# baseSchematicv2sch.net
KiCad netlist of a schematic drawn in EAGLE
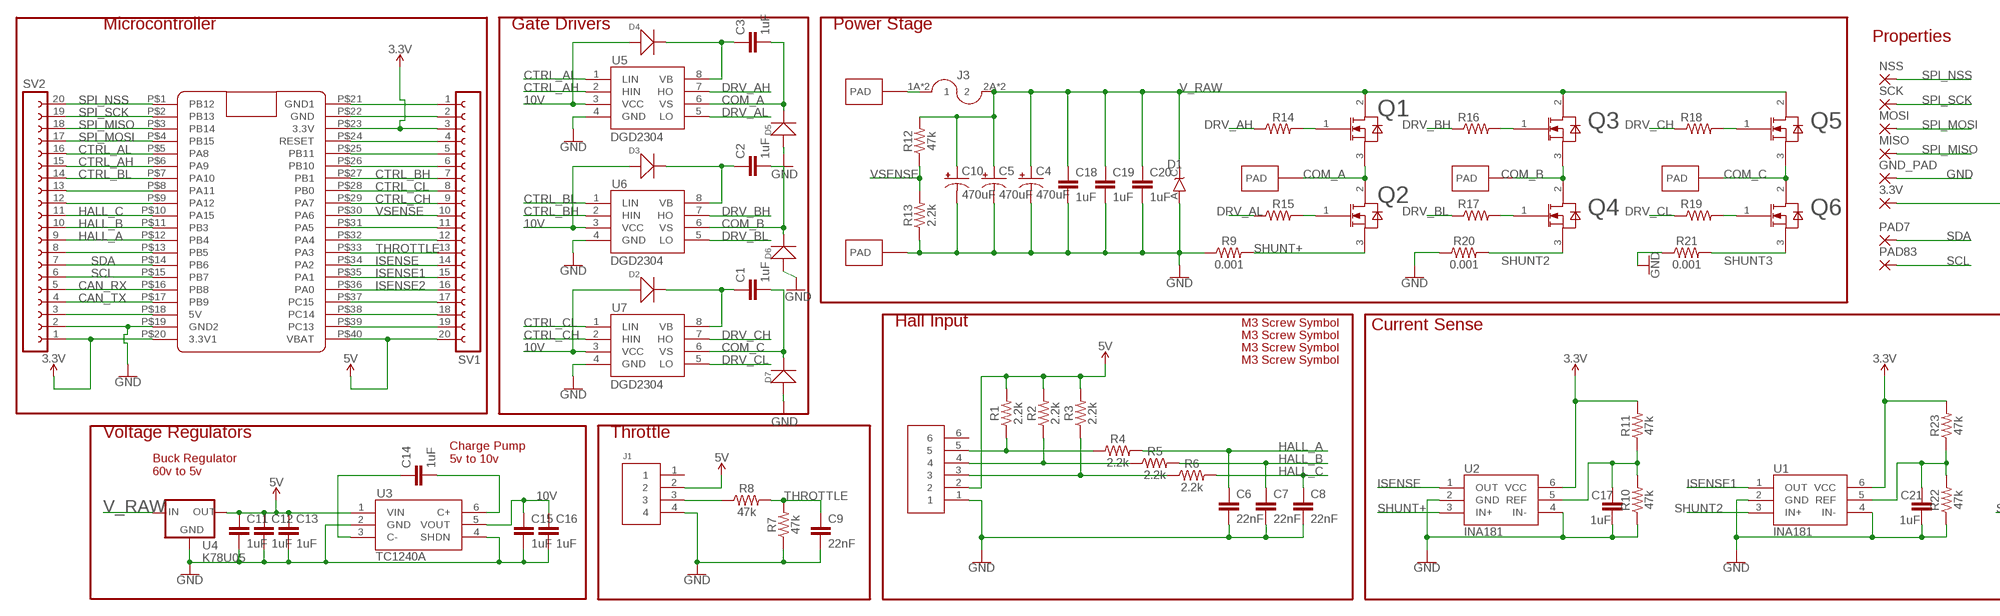
[diagram p0: schematic, sheet 1, part 1 of 2]
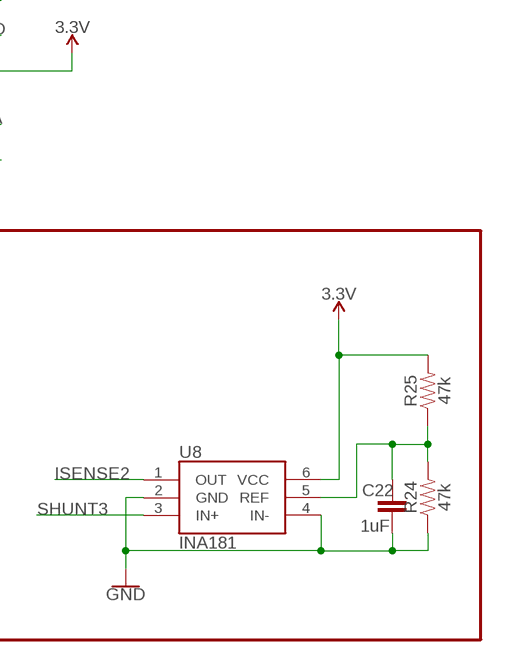
[diagram p1: schematic, sheet 1, part 2 of 2]

(export (version "E")
  (design (tool "Eeschema 10.0.6"))
  (components
    (comp (ref "3.3V")
      (value "2,15/1,0")
      (footprint "eagle-import:2,15_1,0")
      (libsource (lib "eagle-import") (part "2,15/1,0"))
    )
    (comp (ref "C1")
      (value "1uF")
      (footprint "eagle-import:1206")
      (libsource (lib "eagle-import") (part "1.0UF-1206-50V-10%"))
    )
    (comp (ref "C2")
      (value "1uF")
      (footprint "eagle-import:1206")
      (libsource (lib "eagle-import") (part "1.0UF-1206-50V-10%"))
    )
    (comp (ref "C3")
      (value "1uF")
      (footprint "eagle-import:1206")
      (libsource (lib "eagle-import") (part "1.0UF-1206-50V-10%"))
    )
    (comp (ref "C4")
      (value "470uF")
      (footprint "eagle-import:CPOL-RADIAL-5MM-10MM")
      (libsource (lib "eagle-import") (part "1000UF-RADIAL-5MM-25V-20%"))
    )
    (comp (ref "C5")
      (value "470uF")
      (footprint "eagle-import:CPOL-RADIAL-5MM-10MM")
      (libsource (lib "eagle-import") (part "1000UF-RADIAL-5MM-25V-20%"))
    )
    (comp (ref "C6")
      (value "22nF")
      (footprint "eagle-import:1206")
      (libsource (lib "eagle-import") (part "1.0UF-1206-50V-10%"))
    )
    (comp (ref "C7")
      (value "22nF")
      (footprint "eagle-import:1206")
      (libsource (lib "eagle-import") (part "1.0UF-1206-50V-10%"))
    )
    (comp (ref "C8")
      (value "22nF")
      (footprint "eagle-import:1206")
      (libsource (lib "eagle-import") (part "1.0UF-1206-50V-10%"))
    )
    (comp (ref "C9")
      (value "22nF")
      (footprint "eagle-import:1206")
      (libsource (lib "eagle-import") (part "1.0UF-1206-50V-10%"))
    )
    (comp (ref "C10")
      (value "470uF")
      (footprint "eagle-import:CPOL-RADIAL-5MM-10MM")
      (libsource (lib "eagle-import") (part "1000UF-RADIAL-5MM-25V-20%"))
    )
    (comp (ref "C11")
      (value "1uF")
      (footprint "eagle-import:1206")
      (libsource (lib "eagle-import") (part "1.0UF-1206-50V-10%"))
    )
    (comp (ref "C12")
      (value "1uF")
      (footprint "eagle-import:1206")
      (libsource (lib "eagle-import") (part "1.0UF-1206-50V-10%"))
    )
    (comp (ref "C13")
      (value "1uF")
      (footprint "eagle-import:1206")
      (libsource (lib "eagle-import") (part "1.0UF-1206-50V-10%"))
    )
    (comp (ref "C14")
      (value "1uF")
      (footprint "eagle-import:1206")
      (libsource (lib "eagle-import") (part "1.0UF-1206-50V-10%"))
    )
    (comp (ref "C15")
      (value "1uF")
      (footprint "eagle-import:1206")
      (libsource (lib "eagle-import") (part "1.0UF-1206-50V-10%"))
    )
    (comp (ref "C16")
      (value "1uF")
      (footprint "eagle-import:1206")
      (libsource (lib "eagle-import") (part "1.0UF-1206-50V-10%"))
    )
    (comp (ref "C17")
      (value "1uF")
      (footprint "eagle-import:1206")
      (libsource (lib "eagle-import") (part "1.0UF-1206-50V-10%"))
    )
    (comp (ref "C18")
      (value "1uF")
      (footprint "eagle-import:1206")
      (libsource (lib "eagle-import") (part "1.0UF-1206-50V-10%"))
    )
    (comp (ref "C19")
      (value "1uF")
      (footprint "eagle-import:1206")
      (libsource (lib "eagle-import") (part "1.0UF-1206-50V-10%"))
    )
    (comp (ref "C20")
      (value "1uF")
      (footprint "eagle-import:1206")
      (libsource (lib "eagle-import") (part "1.0UF-1206-50V-10%"))
    )
    (comp (ref "C21")
      (value "1uF")
      (footprint "eagle-import:1206")
      (libsource (lib "eagle-import") (part "1.0UF-1206-50V-10%"))
    )
    (comp (ref "C22")
      (value "1uF")
      (footprint "eagle-import:1206")
      (libsource (lib "eagle-import") (part "1.0UF-1206-50V-10%"))
    )
    (comp (ref "D1")
      (value "TVS")
      (footprint "eagle-import:DO-214AC")
      (libsource (lib "eagle-import") (part "TVS_UNIDO-214AC"))
    )
    (comp (ref "D2")
      (value "SMD-DIODE-100V-200MA(SOD-123)")
      (footprint "eagle-import:SOD-123")
      (fields (field (name "MPN") "MMSD4148"))
      (libsource (lib "eagle-import") (part "SMD-DIODE-100V-200MA(SOD-123)"))
    )
    (comp (ref "D3")
      (value "SMD-DIODE-100V-200MA(SOD-123)")
      (footprint "eagle-import:SOD-123")
      (fields (field (name "MPN") "MMSD4148"))
      (libsource (lib "eagle-import") (part "SMD-DIODE-100V-200MA(SOD-123)"))
    )
    (comp (ref "D4")
      (value "SMD-DIODE-100V-200MA(SOD-123)")
      (footprint "eagle-import:SOD-123")
      (fields (field (name "MPN") "MMSD4148"))
      (libsource (lib "eagle-import") (part "SMD-DIODE-100V-200MA(SOD-123)"))
    )
    (comp (ref "D5")
      (value "SMD-DIODE-100V-200MA(SOD-123)")
      (footprint "eagle-import:SOD-123")
      (fields (field (name "MPN") "MMSD4148"))
      (libsource (lib "eagle-import") (part "SMD-DIODE-100V-200MA(SOD-123)"))
    )
    (comp (ref "D6")
      (value "SMD-DIODE-100V-200MA(SOD-123)")
      (footprint "eagle-import:SOD-123")
      (fields (field (name "MPN") "MMSD4148"))
      (libsource (lib "eagle-import") (part "SMD-DIODE-100V-200MA(SOD-123)"))
    )
    (comp (ref "D7")
      (value "SMD-DIODE-100V-200MA(SOD-123)")
      (footprint "eagle-import:SOD-123")
      (fields (field (name "MPN") "MMSD4148"))
      (libsource (lib "eagle-import") (part "SMD-DIODE-100V-200MA(SOD-123)"))
    )
    (comp (ref "GND_PAD")
      (value "2,15/1,0")
      (footprint "eagle-import:2,15_1,0")
      (libsource (lib "eagle-import") (part "2,15/1,0"))
    )
    (comp (ref "J1")
      (value "HEADER4VALULOK")
      (footprint "eagle-import:4PINVALULOK")
      (libsource (lib "eagle-import") (part "HEADER4VALULOK"))
    )
    (comp (ref "J2")
      (value "HEADER6")
      (footprint "eagle-import:6PINVALULOK")
      (libsource (lib "eagle-import") (part "HEADER6"))
    )
    (comp (ref "J3")
      (value "FUSE")
      (footprint "eagle-import:AUTO_FUSE")
      (libsource (lib "eagle-import") (part "FUSE"))
    )
    (comp (ref "MISO")
      (value "2,15/1,0")
      (footprint "eagle-import:2,15_1,0")
      (libsource (lib "eagle-import") (part "2,15/1,0"))
    )
    (comp (ref "MOSI")
      (value "2,15/1,0")
      (footprint "eagle-import:2,15_1,0")
      (libsource (lib "eagle-import") (part "2,15/1,0"))
    )
    (comp (ref "NSS")
      (value "2,15/1,0")
      (footprint "eagle-import:2,15_1,0")
      (libsource (lib "eagle-import") (part "2,15/1,0"))
    )
    (comp (ref "PAD7")
      (value "2,15/1,0")
      (footprint "eagle-import:2,15_1,0")
      (libsource (lib "eagle-import") (part "2,15/1,0"))
    )
    (comp (ref "PAD83")
      (value "2,15/1,0")
      (footprint "eagle-import:2,15_1,0")
      (libsource (lib "eagle-import") (part "2,15/1,0"))
    )
    (comp (ref "Q1")
      (value "IRF135S203")
      (footprint "eagle-import:TO254P1524X508-4_3N")
      (libsource (lib "eagle-import") (part "IRF135S203"))
    )
    (comp (ref "Q2")
      (value "IRF135S203")
      (footprint "eagle-import:TO254P1524X508-4_3N")
      (libsource (lib "eagle-import") (part "IRF135S203"))
    )
    (comp (ref "Q3")
      (value "IRF135S203")
      (footprint "eagle-import:TO254P1524X508-4_3N")
      (libsource (lib "eagle-import") (part "IRF135S203"))
    )
    (comp (ref "Q4")
      (value "IRF135S203")
      (footprint "eagle-import:TO254P1524X508-4_3N")
      (libsource (lib "eagle-import") (part "IRF135S203"))
    )
    (comp (ref "Q5")
      (value "IRF135S203")
      (footprint "eagle-import:TO254P1524X508-4_3N")
      (libsource (lib "eagle-import") (part "IRF135S203"))
    )
    (comp (ref "Q6")
      (value "IRF135S203")
      (footprint "eagle-import:TO254P1524X508-4_3N")
      (libsource (lib "eagle-import") (part "IRF135S203"))
    )
    (comp (ref "R1")
      (value "2.2k")
      (footprint "eagle-import:1206")
      (libsource (lib "eagle-import") (part "RESISTOR1206"))
    )
    (comp (ref "R2")
      (value "2.2k")
      (footprint "eagle-import:1206")
      (libsource (lib "eagle-import") (part "RESISTOR1206"))
    )
    (comp (ref "R3")
      (value "2.2k")
      (footprint "eagle-import:1206")
      (libsource (lib "eagle-import") (part "RESISTOR1206"))
    )
    (comp (ref "R4")
      (value "2.2k")
      (footprint "eagle-import:1206")
      (libsource (lib "eagle-import") (part "RESISTOR1206"))
    )
    (comp (ref "R5")
      (value "2.2k")
      (footprint "eagle-import:1206")
      (libsource (lib "eagle-import") (part "RESISTOR1206"))
    )
    (comp (ref "R6")
      (value "2.2k")
      (footprint "eagle-import:1206")
      (libsource (lib "eagle-import") (part "RESISTOR1206"))
    )
    (comp (ref "R7")
      (value "47k")
      (footprint "eagle-import:1206")
      (libsource (lib "eagle-import") (part "RESISTOR1206"))
    )
    (comp (ref "R8")
      (value "47k")
      (footprint "eagle-import:1206")
      (libsource (lib "eagle-import") (part "RESISTOR1206"))
    )
    (comp (ref "R9")
      (value "0.001")
      (footprint "eagle-import:R2512")
      (libsource (lib "eagle-import") (part "RESISTOR"))
    )
    (comp (ref "R10")
      (value "47k")
      (footprint "eagle-import:1206")
      (libsource (lib "eagle-import") (part "RESISTOR1206"))
    )
    (comp (ref "R11")
      (value "47k")
      (footprint "eagle-import:1206")
      (libsource (lib "eagle-import") (part "RESISTOR1206"))
    )
    (comp (ref "R12")
      (value "47k")
      (footprint "eagle-import:1206")
      (libsource (lib "eagle-import") (part "RESISTOR1206"))
    )
    (comp (ref "R13")
      (value "2.2k")
      (footprint "eagle-import:1206")
      (libsource (lib "eagle-import") (part "RESISTOR1206"))
    )
    (comp (ref "R14")
      (value "R-US_R1206")
      (footprint "eagle-import:R1206")
      (libsource (lib "eagle-import") (part "R-US_R1206"))
    )
    (comp (ref "R15")
      (value "R-US_R1206")
      (footprint "eagle-import:R1206")
      (libsource (lib "eagle-import") (part "R-US_R1206"))
    )
    (comp (ref "R16")
      (value "R-US_R1206")
      (footprint "eagle-import:R1206")
      (libsource (lib "eagle-import") (part "R-US_R1206"))
    )
    (comp (ref "R17")
      (value "R-US_R1206")
      (footprint "eagle-import:R1206")
      (libsource (lib "eagle-import") (part "R-US_R1206"))
    )
    (comp (ref "R18")
      (value "R-US_R1206")
      (footprint "eagle-import:R1206")
      (libsource (lib "eagle-import") (part "R-US_R1206"))
    )
    (comp (ref "R19")
      (value "R-US_R1206")
      (footprint "eagle-import:R1206")
      (libsource (lib "eagle-import") (part "R-US_R1206"))
    )
    (comp (ref "R20")
      (value "0.001")
      (footprint "eagle-import:R2512")
      (libsource (lib "eagle-import") (part "RESISTOR"))
    )
    (comp (ref "R21")
      (value "0.001")
      (footprint "eagle-import:R2512")
      (libsource (lib "eagle-import") (part "RESISTOR"))
    )
    (comp (ref "R22")
      (value "47k")
      (footprint "eagle-import:1206")
      (libsource (lib "eagle-import") (part "RESISTOR1206"))
    )
    (comp (ref "R23")
      (value "47k")
      (footprint "eagle-import:1206")
      (libsource (lib "eagle-import") (part "RESISTOR1206"))
    )
    (comp (ref "R24")
      (value "47k")
      (footprint "eagle-import:1206")
      (libsource (lib "eagle-import") (part "RESISTOR1206"))
    )
    (comp (ref "R25")
      (value "47k")
      (footprint "eagle-import:1206")
      (libsource (lib "eagle-import") (part "RESISTOR1206"))
    )
    (comp (ref "SCK")
      (value "2,15/1,0")
      (footprint "eagle-import:2,15_1,0")
      (libsource (lib "eagle-import") (part "2,15/1,0"))
    )
    (comp (ref "SV1")
      (value "FE20-1")
      (footprint "eagle-import:FE20")
      (libsource (lib "eagle-import") (part "FE20-1"))
    )
    (comp (ref "SV2")
      (value "FE20-1")
      (footprint "eagle-import:FE20")
      (libsource (lib "eagle-import") (part "FE20-1"))
    )
    (comp (ref "U$1")
      (value "BLUE_PILL")
      (footprint "eagle-import:BLUE_PILL")
      (libsource (lib "eagle-import") (part "BLUE_PILL"))
    )
    (comp (ref "U$4")
      (value "PAD")
      (footprint "eagle-import:PAD")
      (libsource (lib "eagle-import") (part "PAD"))
    )
    (comp (ref "U$5")
      (value "PAD")
      (footprint "eagle-import:PAD")
      (libsource (lib "eagle-import") (part "PAD"))
    )
    (comp (ref "U$6")
      (value "PAD")
      (footprint "eagle-import:PAD")
      (libsource (lib "eagle-import") (part "PAD"))
    )
    (comp (ref "U$7")
      (value "PAD")
      (footprint "eagle-import:PAD")
      (libsource (lib "eagle-import") (part "PAD"))
    )
    (comp (ref "U$8")
      (value "PAD")
      (footprint "eagle-import:PAD")
      (libsource (lib "eagle-import") (part "PAD"))
    )
    (comp (ref "U$10")
      (value "SCREW")
      (footprint "eagle-import:M3HOLE")
      (libsource (lib "eagle-import") (part "SCREW"))
    )
    (comp (ref "U$11")
      (value "SCREW")
      (footprint "eagle-import:M3HOLE")
      (libsource (lib "eagle-import") (part "SCREW"))
    )
    (comp (ref "U$12")
      (value "SCREW")
      (footprint "eagle-import:M3HOLE")
      (libsource (lib "eagle-import") (part "SCREW"))
    )
    (comp (ref "U$13")
      (value "SCREW")
      (footprint "eagle-import:M3HOLE")
      (libsource (lib "eagle-import") (part "SCREW"))
    )
    (comp (ref "U1")
      (value "INA181")
      (footprint "eagle-import:SOT23-6")
      (libsource (lib "eagle-import") (part "INA181"))
    )
    (comp (ref "U2")
      (value "INA181")
      (footprint "eagle-import:SOT23-6")
      (libsource (lib "eagle-import") (part "INA181"))
    )
    (comp (ref "U3")
      (value "TC1240A")
      (footprint "eagle-import:SOT23-6")
      (libsource (lib "eagle-import") (part "TC1240A"))
    )
    (comp (ref "U4")
      (value "K78U05")
      (footprint "eagle-import:V78W_BACKWARDS")
      (libsource (lib "eagle-import") (part "V_REG_78XX"))
    )
    (comp (ref "U5")
      (value "DGD2304")
      (footprint "eagle-import:SOIC8")
      (libsource (lib "eagle-import") (part "DGD2304"))
    )
    (comp (ref "U6")
      (value "DGD2304")
      (footprint "eagle-import:SOIC8")
      (libsource (lib "eagle-import") (part "DGD2304"))
    )
    (comp (ref "U7")
      (value "DGD2304")
      (footprint "eagle-import:SOIC8")
      (libsource (lib "eagle-import") (part "DGD2304"))
    )
    (comp (ref "U8")
      (value "INA181")
      (footprint "eagle-import:SOT23-6")
      (libsource (lib "eagle-import") (part "INA181"))
    )
  )
  (nets
    (net (code "1") (name "/10V") (class "Default")
      (node (ref "C15") (pin "1") (pinfunction "1_1") (pintype "passive"))
      (node (ref "C16") (pin "1") (pinfunction "1_1") (pintype "passive"))
      (node (ref "D2") (pin "+") (pinfunction "+_+") (pintype "passive"))
      (node (ref "D3") (pin "+") (pinfunction "+_+") (pintype "passive"))
      (node (ref "D4") (pin "+") (pinfunction "+_+") (pintype "passive"))
      (node (ref "U3") (pin "5") (pinfunction "VOUT_5") (pintype "bidirectional"))
      (node (ref "U5") (pin "3") (pinfunction "VCC_3") (pintype "bidirectional"))
      (node (ref "U6") (pin "3") (pinfunction "VCC_3") (pintype "bidirectional"))
      (node (ref "U7") (pin "3") (pinfunction "VCC_3") (pintype "bidirectional"))
    )
    (net (code "2") (name "/CAN_RX") (class "Default")
      (node (ref "SV2") (pin "5") (pinfunction "5_5") (pintype "passive"))
      (node (ref "U$1") (pin "P$16") (pinfunction "PB8_P$16") (pintype "bidirectional"))
    )
    (net (code "3") (name "/CAN_TX") (class "Default")
      (node (ref "SV2") (pin "4") (pinfunction "4_4") (pintype "passive"))
      (node (ref "U$1") (pin "P$17") (pinfunction "PB9_P$17") (pintype "bidirectional"))
    )
    (net (code "4") (name "/COM_A") (class "Default")
      (node (ref "C3") (pin "2") (pinfunction "2_2") (pintype "passive"))
      (node (ref "D5") (pin "-") (pinfunction "-_-") (pintype "passive"))
      (node (ref "Q1") (pin "3") (pinfunction "SOURCE_3") (pintype "passive"))
      (node (ref "Q2") (pin "2") (pinfunction "DRAIN_2") (pintype "passive"))
      (node (ref "U$6") (pin "PAD") (pinfunction "PAD_PAD") (pintype "bidirectional"))
      (node (ref "U5") (pin "6") (pinfunction "VS_6") (pintype "bidirectional"))
    )
    (net (code "5") (name "/COM_B") (class "Default")
      (node (ref "C2") (pin "2") (pinfunction "2_2") (pintype "passive"))
      (node (ref "D6") (pin "-") (pinfunction "-_-") (pintype "passive"))
      (node (ref "Q3") (pin "3") (pinfunction "SOURCE_3") (pintype "passive"))
      (node (ref "Q4") (pin "2") (pinfunction "DRAIN_2") (pintype "passive"))
      (node (ref "U$7") (pin "PAD") (pinfunction "PAD_PAD") (pintype "bidirectional"))
      (node (ref "U6") (pin "6") (pinfunction "VS_6") (pintype "bidirectional"))
    )
    (net (code "6") (name "/COM_C") (class "Default")
      (node (ref "C1") (pin "2") (pinfunction "2_2") (pintype "passive"))
      (node (ref "D7") (pin "-") (pinfunction "-_-") (pintype "passive"))
      (node (ref "Q5") (pin "3") (pinfunction "SOURCE_3") (pintype "passive"))
      (node (ref "Q6") (pin "2") (pinfunction "DRAIN_2") (pintype "passive"))
      (node (ref "U$8") (pin "PAD") (pinfunction "PAD_PAD") (pintype "bidirectional"))
      (node (ref "U7") (pin "6") (pinfunction "VS_6") (pintype "bidirectional"))
    )
    (net (code "7") (name "/CTRL_AH") (class "Default")
      (node (ref "SV2") (pin "15") (pinfunction "15_15") (pintype "passive"))
      (node (ref "U$1") (pin "P$6") (pinfunction "PA9_P$6") (pintype "bidirectional"))
      (node (ref "U5") (pin "2") (pinfunction "HIN_2") (pintype "bidirectional"))
    )
    (net (code "8") (name "/CTRL_AL") (class "Default")
      (node (ref "SV2") (pin "16") (pinfunction "16_16") (pintype "passive"))
      (node (ref "U$1") (pin "P$5") (pinfunction "PA8_P$5") (pintype "bidirectional"))
      (node (ref "U5") (pin "1") (pinfunction "LIN_1") (pintype "bidirectional"))
    )
    (net (code "9") (name "/CTRL_BH") (class "Default")
      (node (ref "SV1") (pin "7") (pinfunction "7_7") (pintype "passive"))
      (node (ref "U$1") (pin "P$27") (pinfunction "PB1_P$27") (pintype "bidirectional"))
      (node (ref "U6") (pin "2") (pinfunction "HIN_2") (pintype "bidirectional"))
    )
    (net (code "10") (name "/CTRL_BL") (class "Default")
      (node (ref "SV2") (pin "14") (pinfunction "14_14") (pintype "passive"))
      (node (ref "U$1") (pin "P$7") (pinfunction "PA10_P$7") (pintype "bidirectional"))
      (node (ref "U6") (pin "1") (pinfunction "LIN_1") (pintype "bidirectional"))
    )
    (net (code "11") (name "/CTRL_CH") (class "Default")
      (node (ref "SV1") (pin "9") (pinfunction "9_9") (pintype "passive"))
      (node (ref "U$1") (pin "P$29") (pinfunction "PA7_P$29") (pintype "bidirectional"))
      (node (ref "U7") (pin "2") (pinfunction "HIN_2") (pintype "bidirectional"))
    )
    (net (code "12") (name "/CTRL_CL") (class "Default")
      (node (ref "SV1") (pin "8") (pinfunction "8_8") (pintype "passive"))
      (node (ref "U$1") (pin "P$28") (pinfunction "PB0_P$28") (pintype "bidirectional"))
      (node (ref "U7") (pin "1") (pinfunction "LIN_1") (pintype "bidirectional"))
    )
    (net (code "13") (name "/DRV_AH") (class "Default")
      (node (ref "R14") (pin "1") (pinfunction "1_1") (pintype "passive"))
      (node (ref "U5") (pin "7") (pinfunction "HO_7") (pintype "bidirectional"))
    )
    (net (code "14") (name "/DRV_AL") (class "Default")
      (node (ref "R15") (pin "1") (pinfunction "1_1") (pintype "passive"))
      (node (ref "U5") (pin "5") (pinfunction "LO_5") (pintype "bidirectional"))
    )
    (net (code "15") (name "/DRV_BH") (class "Default")
      (node (ref "R16") (pin "1") (pinfunction "1_1") (pintype "passive"))
      (node (ref "U6") (pin "7") (pinfunction "HO_7") (pintype "bidirectional"))
    )
    (net (code "16") (name "/DRV_BL") (class "Default")
      (node (ref "R17") (pin "1") (pinfunction "1_1") (pintype "passive"))
      (node (ref "U6") (pin "5") (pinfunction "LO_5") (pintype "bidirectional"))
    )
    (net (code "17") (name "/DRV_CH") (class "Default")
      (node (ref "R18") (pin "1") (pinfunction "1_1") (pintype "passive"))
      (node (ref "U7") (pin "7") (pinfunction "HO_7") (pintype "bidirectional"))
    )
    (net (code "18") (name "/DRV_CL") (class "Default")
      (node (ref "R19") (pin "1") (pinfunction "1_1") (pintype "passive"))
      (node (ref "U7") (pin "5") (pinfunction "LO_5") (pintype "bidirectional"))
    )
    (net (code "19") (name "/HALL_A") (class "Default")
      (node (ref "C6") (pin "1") (pinfunction "1_1") (pintype "passive"))
      (node (ref "R4") (pin "2") (pinfunction "2_2") (pintype "passive"))
      (node (ref "SV2") (pin "9") (pinfunction "9_9") (pintype "passive"))
      (node (ref "U$1") (pin "P$12") (pinfunction "PB4_P$12") (pintype "bidirectional"))
    )
    (net (code "20") (name "/HALL_B") (class "Default")
      (node (ref "C7") (pin "1") (pinfunction "1_1") (pintype "passive"))
      (node (ref "R5") (pin "2") (pinfunction "2_2") (pintype "passive"))
      (node (ref "SV2") (pin "10") (pinfunction "10_10") (pintype "passive"))
      (node (ref "U$1") (pin "P$11") (pinfunction "PB3_P$11") (pintype "bidirectional"))
    )
    (net (code "21") (name "/HALL_C") (class "Default")
      (node (ref "C8") (pin "1") (pinfunction "1_1") (pintype "passive"))
      (node (ref "R6") (pin "2") (pinfunction "2_2") (pintype "passive"))
      (node (ref "SV2") (pin "11") (pinfunction "11_11") (pintype "passive"))
      (node (ref "U$1") (pin "P$10") (pinfunction "PA15_P$10") (pintype "bidirectional"))
    )
    (net (code "22") (name "/ISENSE") (class "Default")
      (node (ref "SV1") (pin "14") (pinfunction "14_14") (pintype "passive"))
      (node (ref "U$1") (pin "P$34") (pinfunction "PA2_P$34") (pintype "bidirectional"))
      (node (ref "U2") (pin "1") (pinfunction "OUT_1") (pintype "bidirectional"))
    )
    (net (code "23") (name "/ISENSE1") (class "Default")
      (node (ref "SV1") (pin "15") (pinfunction "15_15") (pintype "passive"))
      (node (ref "U$1") (pin "P$35") (pinfunction "PA1_P$35") (pintype "bidirectional"))
      (node (ref "U1") (pin "1") (pinfunction "OUT_1") (pintype "bidirectional"))
    )
    (net (code "24") (name "/ISENSE2") (class "Default")
      (node (ref "SV1") (pin "16") (pinfunction "16_16") (pintype "passive"))
      (node (ref "U$1") (pin "P$36") (pinfunction "PA0_P$36") (pintype "bidirectional"))
      (node (ref "U8") (pin "1") (pinfunction "OUT_1") (pintype "bidirectional"))
    )
    (net (code "25") (name "/SCL") (class "Default")
      (node (ref "PAD83") (pin "1") (pinfunction "P_1") (pintype "passive"))
      (node (ref "SV2") (pin "6") (pinfunction "6_6") (pintype "passive"))
      (node (ref "U$1") (pin "P$15") (pinfunction "PB7_P$15") (pintype "bidirectional"))
    )
    (net (code "26") (name "/SDA") (class "Default")
      (node (ref "PAD7") (pin "1") (pinfunction "P_1") (pintype "passive"))
      (node (ref "SV2") (pin "7") (pinfunction "7_7") (pintype "passive"))
      (node (ref "U$1") (pin "P$14") (pinfunction "PB6_P$14") (pintype "bidirectional"))
    )
    (net (code "27") (name "/SHUNT+") (class "Default")
      (node (ref "Q2") (pin "3") (pinfunction "SOURCE_3") (pintype "passive"))
      (node (ref "R9") (pin "2") (pinfunction "2_2") (pintype "passive"))
      (node (ref "U2") (pin "3") (pinfunction "IN+_3") (pintype "bidirectional"))
    )
    (net (code "28") (name "/SHUNT2") (class "Default")
      (node (ref "Q4") (pin "3") (pinfunction "SOURCE_3") (pintype "passive"))
      (node (ref "R20") (pin "2") (pinfunction "2_2") (pintype "passive"))
      (node (ref "U1") (pin "3") (pinfunction "IN+_3") (pintype "bidirectional"))
    )
    (net (code "29") (name "/SHUNT3") (class "Default")
      (node (ref "Q6") (pin "3") (pinfunction "SOURCE_3") (pintype "passive"))
      (node (ref "R21") (pin "2") (pinfunction "2_2") (pintype "passive"))
      (node (ref "U8") (pin "3") (pinfunction "IN+_3") (pintype "bidirectional"))
    )
    (net (code "30") (name "/SPI_MISO") (class "Default")
      (node (ref "MISO") (pin "1") (pinfunction "P_1") (pintype "passive"))
      (node (ref "SV2") (pin "18") (pinfunction "18_18") (pintype "passive"))
      (node (ref "U$1") (pin "P$3") (pinfunction "PB14_P$3") (pintype "bidirectional"))
    )
    (net (code "31") (name "/SPI_MOSI") (class "Default")
      (node (ref "MOSI") (pin "1") (pinfunction "P_1") (pintype "passive"))
      (node (ref "SV2") (pin "17") (pinfunction "17_17") (pintype "passive"))
      (node (ref "U$1") (pin "P$4") (pinfunction "PB15_P$4") (pintype "bidirectional"))
    )
    (net (code "32") (name "/SPI_NSS") (class "Default")
      (node (ref "NSS") (pin "1") (pinfunction "P_1") (pintype "passive"))
      (node (ref "SV2") (pin "20") (pinfunction "20_20") (pintype "passive"))
      (node (ref "U$1") (pin "P$1") (pinfunction "PB12_P$1") (pintype "bidirectional"))
    )
    (net (code "33") (name "/SPI_SCK") (class "Default")
      (node (ref "SCK") (pin "1") (pinfunction "P_1") (pintype "passive"))
      (node (ref "SV2") (pin "19") (pinfunction "19_19") (pintype "passive"))
      (node (ref "U$1") (pin "P$2") (pinfunction "PB13_P$2") (pintype "bidirectional"))
    )
    (net (code "34") (name "/THROTTLE") (class "Default")
      (node (ref "C9") (pin "1") (pinfunction "1_1") (pintype "passive"))
      (node (ref "R7") (pin "2") (pinfunction "2_2") (pintype "passive"))
      (node (ref "R8") (pin "2") (pinfunction "2_2") (pintype "passive"))
      (node (ref "SV1") (pin "13") (pinfunction "13_13") (pintype "passive"))
      (node (ref "U$1") (pin "P$33") (pinfunction "PA3_P$33") (pintype "bidirectional"))
    )
    (net (code "35") (name "/VSENSE") (class "Default")
      (node (ref "R12") (pin "1") (pinfunction "1_1") (pintype "passive"))
      (node (ref "R13") (pin "2") (pinfunction "2_2") (pintype "passive"))
      (node (ref "SV1") (pin "10") (pinfunction "10_10") (pintype "passive"))
      (node (ref "U$1") (pin "P$30") (pinfunction "PA6_P$30") (pintype "bidirectional"))
    )
    (net (code "36") (name "/V_RAW") (class "Default")
      (node (ref "C10") (pin "+") (pinfunction "+_+") (pintype "passive"))
      (node (ref "C18") (pin "1") (pinfunction "1_1") (pintype "passive"))
      (node (ref "C19") (pin "1") (pinfunction "1_1") (pintype "passive"))
      (node (ref "C20") (pin "1") (pinfunction "1_1") (pintype "passive"))
      (node (ref "C4") (pin "+") (pinfunction "+_+") (pintype "passive"))
      (node (ref "C5") (pin "+") (pinfunction "+_+") (pintype "passive"))
      (node (ref "D1") (pin "C") (pinfunction "C_C") (pintype "bidirectional"))
      (node (ref "J3") (pin "2A") (pinfunction "2_2A") (pintype "bidirectional"))
      (node (ref "J3") (pin "2B") (pinfunction "2_2B") (pintype "bidirectional"))
      (node (ref "Q1") (pin "2") (pinfunction "DRAIN_2") (pintype "passive"))
      (node (ref "Q3") (pin "2") (pinfunction "DRAIN_2") (pintype "passive"))
      (node (ref "Q5") (pin "2") (pinfunction "DRAIN_2") (pintype "passive"))
      (node (ref "R12") (pin "2") (pinfunction "2_2") (pintype "passive"))
      (node (ref "U4") (pin "IN") (pinfunction "IN_IN") (pintype "input"))
    )
    (net (code "37") (name "3.3V") (class "Default")
      (node (ref "3.3V") (pin "1") (pinfunction "P_1") (pintype "passive"))
      (node (ref "R11") (pin "2") (pinfunction "2_2") (pintype "passive"))
      (node (ref "R23") (pin "2") (pinfunction "2_2") (pintype "passive"))
      (node (ref "R25") (pin "2") (pinfunction "2_2") (pintype "passive"))
      (node (ref "SV1") (pin "3") (pinfunction "3_3") (pintype "passive"))
      (node (ref "SV2") (pin "1") (pinfunction "1_1") (pintype "passive"))
      (node (ref "U$1") (pin "P$20") (pinfunction "3.3V1_P$20") (pintype "bidirectional"))
      (node (ref "U$1") (pin "P$23") (pinfunction "3.3V_P$23") (pintype "bidirectional"))
      (node (ref "U1") (pin "6") (pinfunction "VCC_6") (pintype "bidirectional"))
      (node (ref "U2") (pin "6") (pinfunction "VCC_6") (pintype "bidirectional"))
      (node (ref "U8") (pin "6") (pinfunction "VCC_6") (pintype "bidirectional"))
    )
    (net (code "38") (name "5V") (class "Default")
      (node (ref "C11") (pin "1") (pinfunction "1_1") (pintype "passive"))
      (node (ref "C12") (pin "1") (pinfunction "1_1") (pintype "passive"))
      (node (ref "C13") (pin "1") (pinfunction "1_1") (pintype "passive"))
      (node (ref "J1") (pin "2") (pinfunction "2_2") (pintype "bidirectional"))
      (node (ref "J2") (pin "2") (pinfunction "2_2") (pintype "bidirectional"))
      (node (ref "R1") (pin "2") (pinfunction "2_2") (pintype "passive"))
      (node (ref "R2") (pin "2") (pinfunction "2_2") (pintype "passive"))
      (node (ref "R3") (pin "2") (pinfunction "2_2") (pintype "passive"))
      (node (ref "SV1") (pin "20") (pinfunction "20_20") (pintype "passive"))
      (node (ref "U$1") (pin "P$40") (pinfunction "VBAT_P$40") (pintype "bidirectional"))
      (node (ref "U3") (pin "1") (pinfunction "VIN_1") (pintype "bidirectional"))
      (node (ref "U4") (pin "OUT") (pinfunction "OUT_OUT") (pintype "output"))
    )
    (net (code "39") (name "GND") (class "Default")
      (node (ref "C10") (pin "-") (pinfunction "-_-") (pintype "passive"))
      (node (ref "C11") (pin "2") (pinfunction "2_2") (pintype "passive"))
      (node (ref "C12") (pin "2") (pinfunction "2_2") (pintype "passive"))
      (node (ref "C13") (pin "2") (pinfunction "2_2") (pintype "passive"))
      (node (ref "C15") (pin "2") (pinfunction "2_2") (pintype "passive"))
      (node (ref "C16") (pin "2") (pinfunction "2_2") (pintype "passive"))
      (node (ref "C17") (pin "2") (pinfunction "2_2") (pintype "passive"))
      (node (ref "C18") (pin "2") (pinfunction "2_2") (pintype "passive"))
      (node (ref "C19") (pin "2") (pinfunction "2_2") (pintype "passive"))
      (node (ref "C20") (pin "2") (pinfunction "2_2") (pintype "passive"))
      (node (ref "C21") (pin "2") (pinfunction "2_2") (pintype "passive"))
      (node (ref "C22") (pin "2") (pinfunction "2_2") (pintype "passive"))
      (node (ref "C4") (pin "-") (pinfunction "-_-") (pintype "passive"))
      (node (ref "C5") (pin "-") (pinfunction "-_-") (pintype "passive"))
      (node (ref "C6") (pin "2") (pinfunction "2_2") (pintype "passive"))
      (node (ref "C7") (pin "2") (pinfunction "2_2") (pintype "passive"))
      (node (ref "C8") (pin "2") (pinfunction "2_2") (pintype "passive"))
      (node (ref "C9") (pin "2") (pinfunction "2_2") (pintype "passive"))
      (node (ref "D1") (pin "A") (pinfunction "A_A") (pintype "bidirectional"))
      (node (ref "D5") (pin "+") (pinfunction "+_+") (pintype "passive"))
      (node (ref "D6") (pin "+") (pinfunction "+_+") (pintype "passive"))
      (node (ref "D7") (pin "+") (pinfunction "+_+") (pintype "passive"))
      (node (ref "GND_PAD") (pin "1") (pinfunction "P_1") (pintype "passive"))
      (node (ref "J1") (pin "4") (pinfunction "4_4") (pintype "bidirectional"))
      (node (ref "J2") (pin "1") (pinfunction "1_1") (pintype "bidirectional"))
      (node (ref "R10") (pin "1") (pinfunction "1_1") (pintype "passive"))
      (node (ref "R13") (pin "1") (pinfunction "1_1") (pintype "passive"))
      (node (ref "R20") (pin "1") (pinfunction "1_1") (pintype "passive"))
      (node (ref "R21") (pin "1") (pinfunction "1_1") (pintype "passive"))
      (node (ref "R22") (pin "1") (pinfunction "1_1") (pintype "passive"))
      (node (ref "R24") (pin "1") (pinfunction "1_1") (pintype "passive"))
      (node (ref "R7") (pin "1") (pinfunction "1_1") (pintype "passive"))
      (node (ref "R9") (pin "1") (pinfunction "1_1") (pintype "passive"))
      (node (ref "SV2") (pin "2") (pinfunction "2_2") (pintype "passive"))
      (node (ref "U$1") (pin "P$19") (pinfunction "GND2_P$19") (pintype "bidirectional"))
      (node (ref "U$5") (pin "PAD") (pinfunction "PAD_PAD") (pintype "bidirectional"))
      (node (ref "U1") (pin "2") (pinfunction "GND_2") (pintype "bidirectional"))
      (node (ref "U1") (pin "4") (pinfunction "IN-_4") (pintype "bidirectional"))
      (node (ref "U2") (pin "2") (pinfunction "GND_2") (pintype "bidirectional"))
      (node (ref "U2") (pin "4") (pinfunction "IN-_4") (pintype "bidirectional"))
      (node (ref "U3") (pin "2") (pinfunction "GND_2") (pintype "bidirectional"))
      (node (ref "U3") (pin "4") (pinfunction "SHDN_4") (pintype "bidirectional"))
      (node (ref "U4") (pin "GND") (pinfunction "GND_GND") (pintype "input"))
      (node (ref "U5") (pin "4") (pinfunction "GND_4") (pintype "bidirectional"))
      (node (ref "U6") (pin "4") (pinfunction "GND_4") (pintype "bidirectional"))
      (node (ref "U7") (pin "4") (pinfunction "GND_4") (pintype "bidirectional"))
      (node (ref "U8") (pin "2") (pinfunction "GND_2") (pintype "bidirectional"))
      (node (ref "U8") (pin "4") (pinfunction "IN-_4") (pintype "bidirectional"))
    )
    (net (code "40") (name "Net-(J1-Pad3)") (class "Default")
      (node (ref "J1") (pin "3") (pinfunction "3_3") (pintype "bidirectional"))
      (node (ref "R8") (pin "1") (pinfunction "1_1") (pintype "passive"))
    )
    (net (code "41") (name "Net-(J2-Pad3)") (class "Default")
      (node (ref "J2") (pin "3") (pinfunction "3_3") (pintype "bidirectional"))
      (node (ref "R3") (pin "1") (pinfunction "1_1") (pintype "passive"))
      (node (ref "R6") (pin "1") (pinfunction "1_1") (pintype "passive"))
    )
    (net (code "42") (name "Net-(J2-Pad4)") (class "Default")
      (node (ref "J2") (pin "4") (pinfunction "4_4") (pintype "bidirectional"))
      (node (ref "R2") (pin "1") (pinfunction "1_1") (pintype "passive"))
      (node (ref "R5") (pin "1") (pinfunction "1_1") (pintype "passive"))
    )
    (net (code "43") (name "Net-(J2-Pad5)") (class "Default")
      (node (ref "J2") (pin "5") (pinfunction "5_5") (pintype "bidirectional"))
      (node (ref "R1") (pin "1") (pinfunction "1_1") (pintype "passive"))
      (node (ref "R4") (pin "1") (pinfunction "1_1") (pintype "passive"))
    )
    (net (code "44") (name "Net-(J3-1-Pad1A)") (class "Default")
      (node (ref "J3") (pin "1A") (pinfunction "1_1A") (pintype "bidirectional"))
      (node (ref "J3") (pin "1B") (pinfunction "1_1B") (pintype "bidirectional"))
      (node (ref "U$4") (pin "PAD") (pinfunction "PAD_PAD") (pintype "bidirectional"))
    )
    (net (code "45") (name "Net-(Q1-GATE)") (class "Default")
      (node (ref "Q1") (pin "1") (pinfunction "GATE_1") (pintype "passive"))
      (node (ref "R14") (pin "2") (pinfunction "2_2") (pintype "passive"))
    )
    (net (code "46") (name "Net-(Q2-GATE)") (class "Default")
      (node (ref "Q2") (pin "1") (pinfunction "GATE_1") (pintype "passive"))
      (node (ref "R15") (pin "2") (pinfunction "2_2") (pintype "passive"))
    )
    (net (code "47") (name "Net-(Q3-GATE)") (class "Default")
      (node (ref "Q3") (pin "1") (pinfunction "GATE_1") (pintype "passive"))
      (node (ref "R16") (pin "2") (pinfunction "2_2") (pintype "passive"))
    )
    (net (code "48") (name "Net-(Q4-GATE)") (class "Default")
      (node (ref "Q4") (pin "1") (pinfunction "GATE_1") (pintype "passive"))
      (node (ref "R17") (pin "2") (pinfunction "2_2") (pintype "passive"))
    )
    (net (code "49") (name "Net-(Q5-GATE)") (class "Default")
      (node (ref "Q5") (pin "1") (pinfunction "GATE_1") (pintype "passive"))
      (node (ref "R18") (pin "2") (pinfunction "2_2") (pintype "passive"))
    )
    (net (code "50") (name "Net-(Q6-GATE)") (class "Default")
      (node (ref "Q6") (pin "1") (pinfunction "GATE_1") (pintype "passive"))
      (node (ref "R19") (pin "2") (pinfunction "2_2") (pintype "passive"))
    )
    (net (code "51") (name "Net-(U$1-5V)") (class "Default")
      (node (ref "SV2") (pin "3") (pinfunction "3_3") (pintype "passive"))
      (node (ref "U$1") (pin "P$18") (pinfunction "5V_P$18") (pintype "bidirectional"))
    )
    (net (code "52") (name "Net-(U$1-GND)") (class "Default")
      (node (ref "SV1") (pin "2") (pinfunction "2_2") (pintype "passive"))
      (node (ref "U$1") (pin "P$22") (pinfunction "GND_P$22") (pintype "bidirectional"))
    )
    (net (code "53") (name "Net-(U$1-GND1)") (class "Default")
      (node (ref "SV1") (pin "1") (pinfunction "1_1") (pintype "passive"))
      (node (ref "U$1") (pin "P$21") (pinfunction "GND1_P$21") (pintype "power_in"))
    )
    (net (code "54") (name "Net-(U$1-PA4)") (class "Default")
      (node (ref "SV1") (pin "12") (pinfunction "12_12") (pintype "passive"))
      (node (ref "U$1") (pin "P$32") (pinfunction "PA4_P$32") (pintype "bidirectional"))
    )
    (net (code "55") (name "Net-(U$1-PA5)") (class "Default")
      (node (ref "SV1") (pin "11") (pinfunction "11_11") (pintype "passive"))
      (node (ref "U$1") (pin "P$31") (pinfunction "PA5_P$31") (pintype "bidirectional"))
    )
    (net (code "56") (name "Net-(U$1-PA11)") (class "Default")
      (node (ref "SV2") (pin "13") (pinfunction "13_13") (pintype "passive"))
      (node (ref "U$1") (pin "P$8") (pinfunction "PA11_P$8") (pintype "bidirectional"))
    )
    (net (code "57") (name "Net-(U$1-PA12)") (class "Default")
      (node (ref "SV2") (pin "12") (pinfunction "12_12") (pintype "passive"))
      (node (ref "U$1") (pin "P$9") (pinfunction "PA12_P$9") (pintype "bidirectional"))
    )
    (net (code "58") (name "Net-(U$1-PB5)") (class "Default")
      (node (ref "SV2") (pin "8") (pinfunction "8_8") (pintype "passive"))
      (node (ref "U$1") (pin "P$13") (pinfunction "PB5_P$13") (pintype "bidirectional"))
    )
    (net (code "59") (name "Net-(U$1-PB10)") (class "Default")
      (node (ref "SV1") (pin "6") (pinfunction "6_6") (pintype "passive"))
      (node (ref "U$1") (pin "P$26") (pinfunction "PB10_P$26") (pintype "bidirectional"))
    )
    (net (code "60") (name "Net-(U$1-PB11)") (class "Default")
      (node (ref "SV1") (pin "5") (pinfunction "5_5") (pintype "passive"))
      (node (ref "U$1") (pin "P$25") (pinfunction "PB11_P$25") (pintype "bidirectional"))
    )
    (net (code "61") (name "Net-(U$1-PC13)") (class "Default")
      (node (ref "SV1") (pin "19") (pinfunction "19_19") (pintype "passive"))
      (node (ref "U$1") (pin "P$39") (pinfunction "PC13_P$39") (pintype "bidirectional"))
    )
    (net (code "62") (name "Net-(U$1-PC14)") (class "Default")
      (node (ref "SV1") (pin "18") (pinfunction "18_18") (pintype "passive"))
      (node (ref "U$1") (pin "P$38") (pinfunction "PC14_P$38") (pintype "bidirectional"))
    )
    (net (code "63") (name "Net-(U$1-PC15)") (class "Default")
      (node (ref "SV1") (pin "17") (pinfunction "17_17") (pintype "passive"))
      (node (ref "U$1") (pin "P$37") (pinfunction "PC15_P$37") (pintype "bidirectional"))
    )
    (net (code "64") (name "Net-(U$1-RESET)") (class "Default")
      (node (ref "SV1") (pin "4") (pinfunction "4_4") (pintype "passive"))
      (node (ref "U$1") (pin "P$24") (pinfunction "RESET_P$24") (pintype "bidirectional"))
    )
    (net (code "65") (name "Net-(U1-REF)") (class "Default")
      (node (ref "C21") (pin "1") (pinfunction "1_1") (pintype "passive"))
      (node (ref "R22") (pin "2") (pinfunction "2_2") (pintype "passive"))
      (node (ref "R23") (pin "1") (pinfunction "1_1") (pintype "passive"))
      (node (ref "U1") (pin "5") (pinfunction "REF_5") (pintype "bidirectional"))
    )
    (net (code "66") (name "Net-(U2-REF)") (class "Default")
      (node (ref "C17") (pin "1") (pinfunction "1_1") (pintype "passive"))
      (node (ref "R10") (pin "2") (pinfunction "2_2") (pintype "passive"))
      (node (ref "R11") (pin "1") (pinfunction "1_1") (pintype "passive"))
      (node (ref "U2") (pin "5") (pinfunction "REF_5") (pintype "bidirectional"))
    )
    (net (code "67") (name "Net-(U3-C+)") (class "Default")
      (node (ref "C14") (pin "2") (pinfunction "2_2") (pintype "passive"))
      (node (ref "U3") (pin "6") (pinfunction "C+_6") (pintype "bidirectional"))
    )
    (net (code "68") (name "Net-(U3-C-)") (class "Default")
      (node (ref "C14") (pin "1") (pinfunction "1_1") (pintype "passive"))
      (node (ref "U3") (pin "3") (pinfunction "C-_3") (pintype "bidirectional"))
    )
    (net (code "69") (name "Net-(U5-VB)") (class "Default")
      (node (ref "C3") (pin "1") (pinfunction "1_1") (pintype "passive"))
      (node (ref "D4") (pin "-") (pinfunction "-_-") (pintype "passive"))
      (node (ref "U5") (pin "8") (pinfunction "VB_8") (pintype "bidirectional"))
    )
    (net (code "70") (name "Net-(U6-VB)") (class "Default")
      (node (ref "C2") (pin "1") (pinfunction "1_1") (pintype "passive"))
      (node (ref "D3") (pin "-") (pinfunction "-_-") (pintype "passive"))
      (node (ref "U6") (pin "8") (pinfunction "VB_8") (pintype "bidirectional"))
    )
    (net (code "71") (name "Net-(U7-VB)") (class "Default")
      (node (ref "C1") (pin "1") (pinfunction "1_1") (pintype "passive"))
      (node (ref "D2") (pin "-") (pinfunction "-_-") (pintype "passive"))
      (node (ref "U7") (pin "8") (pinfunction "VB_8") (pintype "bidirectional"))
    )
    (net (code "72") (name "Net-(U8-REF)") (class "Default")
      (node (ref "C22") (pin "1") (pinfunction "1_1") (pintype "passive"))
      (node (ref "R24") (pin "2") (pinfunction "2_2") (pintype "passive"))
      (node (ref "R25") (pin "1") (pinfunction "1_1") (pintype "passive"))
      (node (ref "U8") (pin "5") (pinfunction "REF_5") (pintype "bidirectional"))
    )
    (net (code "73") (name "unconnected-(J1-Pad1)") (class "Default")
      (node (ref "J1") (pin "1") (pinfunction "1_1") (pintype "bidirectional"))
    )
    (net (code "74") (name "unconnected-(J2-Pad6)") (class "Default")
      (node (ref "J2") (pin "6") (pinfunction "6_6") (pintype "bidirectional"))
    )
  )
)
